# main.net
KiCad netlist of a schematic drawn in Altium Designer
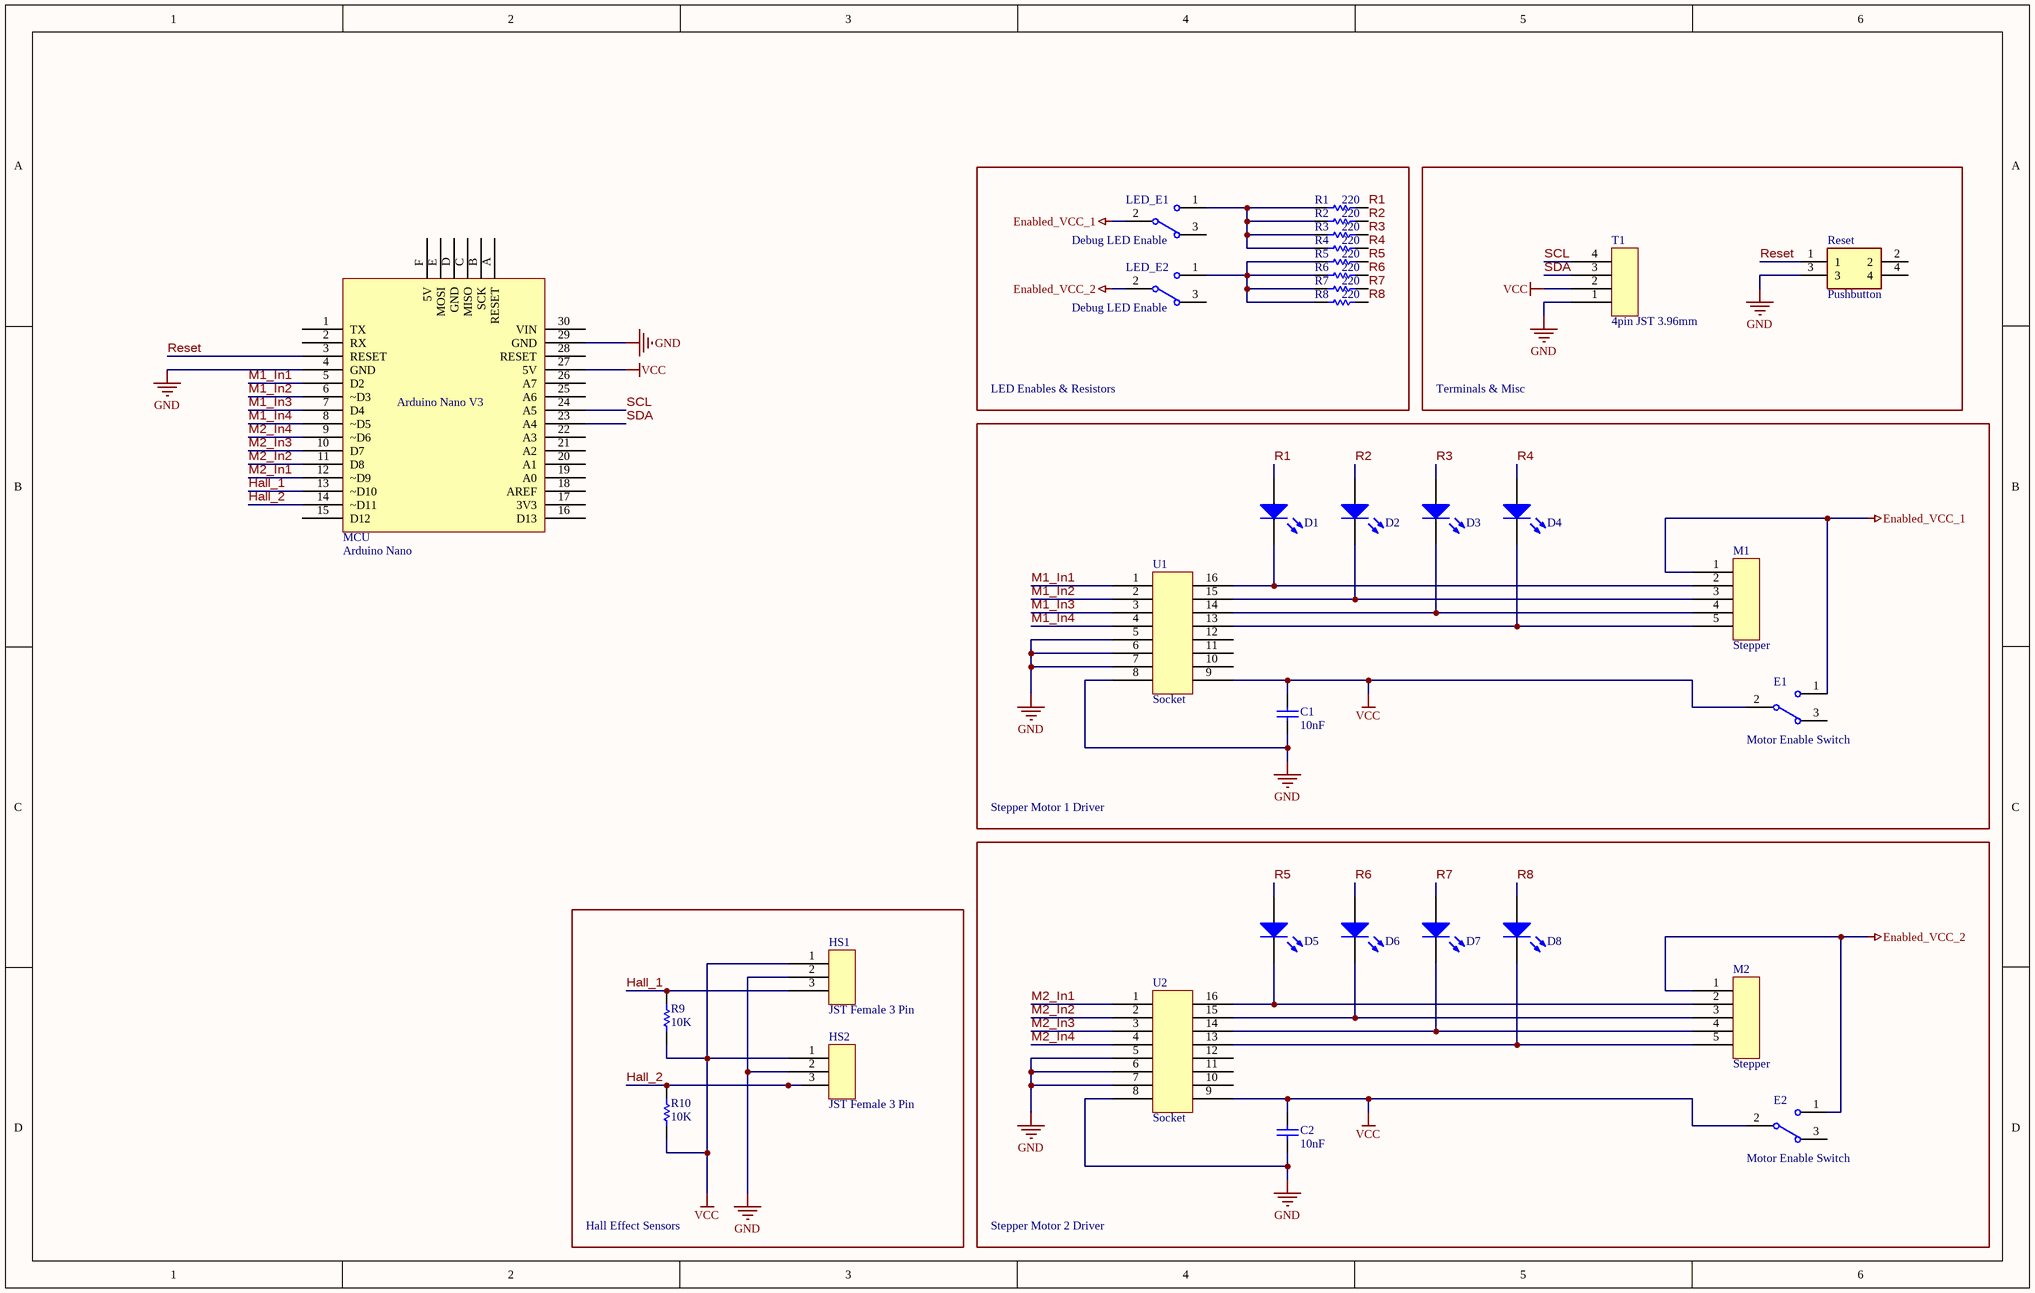
[diagram p0: main.SchDoc]

(export (version "E")
  (design (tool "Eeschema 10.0.6"))
  (components
    (comp (ref "C1")
      (value "Thru-Hole Cap")
      (footprint "Nonpolarized cap")
      (description "Nonpolarized capacitor")
      (fields (field (name "CAPACITANCE") "10nF"))
      (libsource (lib "Misc Components") (part "Thru-Hole Cap"))
    )
    (comp (ref "C2")
      (value "Thru-Hole Cap")
      (footprint "Nonpolarized cap")
      (description "Nonpolarized capacitor")
      (fields (field (name "CAPACITANCE") "10nF"))
      (libsource (lib "Misc Components") (part "Thru-Hole Cap"))
    )
    (comp (ref "D1")
      (value "LED")
      (footprint "Small Blue LED")
      (description "3mm LED")
      (libsource (lib "Misc Components") (part "Small LED"))
    )
    (comp (ref "D2")
      (value "LED")
      (footprint "Small Green LED")
      (description "3mm LED")
      (libsource (lib "Misc Components") (part "Small LED"))
    )
    (comp (ref "D3")
      (value "LED")
      (footprint "Small Orange LED")
      (description "3mm LED")
      (libsource (lib "Misc Components") (part "Small LED"))
    )
    (comp (ref "D4")
      (value "LED")
      (footprint "Small Yellow LED")
      (description "3mm LED")
      (libsource (lib "Misc Components") (part "Small LED"))
    )
    (comp (ref "D5")
      (value "LED")
      (footprint "Small Blue LED")
      (description "3mm LED")
      (libsource (lib "Misc Components") (part "Small LED"))
    )
    (comp (ref "D6")
      (value "LED")
      (footprint "Small Green LED")
      (description "3mm LED")
      (libsource (lib "Misc Components") (part "Small LED"))
    )
    (comp (ref "D7")
      (value "LED")
      (footprint "Small Orange LED")
      (description "3mm LED")
      (libsource (lib "Misc Components") (part "Small LED"))
    )
    (comp (ref "D8")
      (value "LED")
      (footprint "Small Yellow LED")
      (description "3mm LED")
      (libsource (lib "Misc Components") (part "Small LED"))
    )
    (comp (ref "E1")
      (value "Motor Enable Switch")
      (footprint "SPDT Switch")
      (libsource (lib "Misc Components") (part "SPDT Switch"))
    )
    (comp (ref "E2")
      (value "Motor Enable Switch")
      (footprint "SPDT Switch")
      (libsource (lib "Misc Components") (part "SPDT Switch"))
    )
    (comp (ref "HS1")
      (value "JST Female 3 Pin")
      (footprint "Jst Female 3pin")
      (libsource (lib "Misc Components") (part "JST Female 3 Pin"))
    )
    (comp (ref "HS2")
      (value "JST Female 3 Pin")
      (footprint "Jst Female 3pin")
      (libsource (lib "Misc Components") (part "JST Female 3 Pin"))
    )
    (comp (ref "LED_E1")
      (value "Debug LED Enable")
      (footprint "SPDT Switch")
      (libsource (lib "Misc Components") (part "SPDT Switch"))
    )
    (comp (ref "LED_E2")
      (value "Debug LED Enable")
      (footprint "SPDT Switch")
      (libsource (lib "Misc Components") (part "SPDT Switch"))
    )
    (comp (ref "M1")
      (value "Stepper")
      (footprint "JST Female 5pin")
      (libsource (lib "Misc Components") (part "JST Female 5 Pin"))
    )
    (comp (ref "M2")
      (value "Stepper")
      (footprint "JST Female 5pin")
      (libsource (lib "Misc Components") (part "JST Female 5 Pin"))
    )
    (comp (ref "MCU")
      (value "Arduino Nano")
      (footprint "Arduino Nano")
      (libsource (lib "Detailed Arduino") (part "Arduino Nano"))
    )
    (comp (ref "R1")
      (value "220")
      (footprint "AXIAL-0.3")
      (description "Resistor")
      (fields (field (name "Comment") "Res1") (field (name "PUBLISHER") "Altium Limited"))
      (libsource (lib "Miscellaneous Devices") (part "Res1"))
    )
    (comp (ref "R2")
      (value "220")
      (footprint "AXIAL-0.3")
      (description "Resistor")
      (fields (field (name "Comment") "Res1") (field (name "PUBLISHER") "Altium Limited"))
      (libsource (lib "Miscellaneous Devices") (part "Res1"))
    )
    (comp (ref "R3")
      (value "220")
      (footprint "AXIAL-0.3")
      (description "Resistor")
      (fields (field (name "Comment") "Res1") (field (name "PUBLISHER") "Altium Limited"))
      (libsource (lib "Miscellaneous Devices") (part "Res1"))
    )
    (comp (ref "R4")
      (value "220")
      (footprint "AXIAL-0.3")
      (description "Resistor")
      (fields (field (name "Comment") "Res1") (field (name "PUBLISHER") "Altium Limited"))
      (libsource (lib "Miscellaneous Devices") (part "Res1"))
    )
    (comp (ref "R5")
      (value "220")
      (footprint "AXIAL-0.3")
      (description "Resistor")
      (fields (field (name "Comment") "Res1") (field (name "PUBLISHER") "Altium Limited"))
      (libsource (lib "Miscellaneous Devices") (part "Res1"))
    )
    (comp (ref "R6")
      (value "220")
      (footprint "AXIAL-0.3")
      (description "Resistor")
      (fields (field (name "Comment") "Res1") (field (name "PUBLISHER") "Altium Limited"))
      (libsource (lib "Miscellaneous Devices") (part "Res1"))
    )
    (comp (ref "R7")
      (value "220")
      (footprint "AXIAL-0.3")
      (description "Resistor")
      (fields (field (name "Comment") "Res1") (field (name "PUBLISHER") "Altium Limited"))
      (libsource (lib "Miscellaneous Devices") (part "Res1"))
    )
    (comp (ref "R8")
      (value "220")
      (footprint "AXIAL-0.3")
      (description "Resistor")
      (fields (field (name "Comment") "Res1") (field (name "PUBLISHER") "Altium Limited"))
      (libsource (lib "Miscellaneous Devices") (part "Res1"))
    )
    (comp (ref "R9")
      (value "10K")
      (footprint "AXIAL-0.3")
      (description "Resistor")
      (fields (field (name "Comment") "Res1") (field (name "PUBLISHER") "Altium Limited"))
      (libsource (lib "Miscellaneous Devices") (part "Res1"))
    )
    (comp (ref "R10")
      (value "10K")
      (footprint "AXIAL-0.3")
      (description "Resistor")
      (fields (field (name "Comment") "Res1") (field (name "PUBLISHER") "Altium Limited"))
      (libsource (lib "Miscellaneous Devices") (part "Res1"))
    )
    (comp (ref "Reset")
      (value "Pushbutton")
      (footprint "SamacSys:FSM4JH")
      (description "Switch")
      (fields
        (field (name "MANUFACTURER_PART_NUMBER") "FSM2JAH")
        (field (name "MOUSER PART NUMBER") "506-FSM2JAH")
      )
      (libsource (lib "SamacSys") (part "Pushbutton"))
    )
    (comp (ref "T1")
      (value "4pin JST 3.96mm")
      (footprint "JST VH 3.96mm 4pin Female Connector")
      (libsource (lib "Misc Components") (part "JST VH 3.96mm 4pin Female Connector"))
    )
    (comp (ref "U1")
      (value "Socket")
      (footprint "SamacSys:16pin DIP IC Socket")
      (description "Integrated Circuit")
      (fields
        (field (name "MANUFACTURER_PART_NUMBER") "1-2199298-4")
        (field (name "MOUSER PART NUMBER") "571-1-2199298-4")
      )
      (libsource (lib "SamacSys") (part "1-2199298-4"))
    )
    (comp (ref "U2")
      (value "Socket")
      (footprint "SamacSys:16pin DIP IC Socket")
      (description "Integrated Circuit")
      (fields
        (field (name "MANUFACTURER_PART_NUMBER") "1-2199298-4")
        (field (name "MOUSER PART NUMBER") "571-1-2199298-4")
      )
      (libsource (lib "SamacSys") (part "1-2199298-4"))
    )
  )
  (nets
    (net (code "1") (name "/Hall_1") (class "Default")
      (node (ref "HS1") (pin "3") (pintype "power_in"))
      (node (ref "MCU") (pin "13") (pinfunction "~D10_13") (pintype "power_in"))
      (node (ref "R9") (pin "1") (pinfunction "1_1") (pintype "passive"))
    )
    (net (code "2") (name "/Hall_2") (class "Default")
      (node (ref "HS2") (pin "3") (pintype "power_in"))
      (node (ref "MCU") (pin "14") (pinfunction "~D11_14") (pintype "power_in"))
      (node (ref "R10") (pin "1") (pinfunction "1_1") (pintype "passive"))
    )
    (net (code "3") (name "/M1_In1") (class "Default")
      (node (ref "MCU") (pin "5") (pinfunction "D2_5") (pintype "power_in"))
      (node (ref "U1") (pin "1") (pintype "power_in"))
    )
    (net (code "4") (name "/M1_In2") (class "Default")
      (node (ref "MCU") (pin "6") (pinfunction "~D3_6") (pintype "power_in"))
      (node (ref "U1") (pin "2") (pintype "power_in"))
    )
    (net (code "5") (name "/M1_In3") (class "Default")
      (node (ref "MCU") (pin "7") (pinfunction "D4_7") (pintype "power_in"))
      (node (ref "U1") (pin "3") (pintype "power_in"))
    )
    (net (code "6") (name "/M1_In4") (class "Default")
      (node (ref "MCU") (pin "8") (pinfunction "~D5_8") (pintype "power_in"))
      (node (ref "U1") (pin "4") (pintype "power_in"))
    )
    (net (code "7") (name "/M2_In1") (class "Default")
      (node (ref "MCU") (pin "12") (pinfunction "~D9_12") (pintype "power_in"))
      (node (ref "U2") (pin "1") (pintype "power_in"))
    )
    (net (code "8") (name "/M2_In2") (class "Default")
      (node (ref "MCU") (pin "11") (pinfunction "D8_11") (pintype "power_in"))
      (node (ref "U2") (pin "2") (pintype "power_in"))
    )
    (net (code "9") (name "/M2_In3") (class "Default")
      (node (ref "MCU") (pin "10") (pinfunction "D7_10") (pintype "power_in"))
      (node (ref "U2") (pin "3") (pintype "power_in"))
    )
    (net (code "10") (name "/M2_In4") (class "Default")
      (node (ref "MCU") (pin "9") (pinfunction "~D6_9") (pintype "power_in"))
      (node (ref "U2") (pin "4") (pintype "power_in"))
    )
    (net (code "11") (name "/R1") (class "Default")
      (node (ref "D1") (pin "1") (pinfunction "A_1") (pintype "passive"))
      (node (ref "R1") (pin "2") (pinfunction "2_2") (pintype "passive"))
    )
    (net (code "12") (name "/R2") (class "Default")
      (node (ref "D2") (pin "1") (pinfunction "A_1") (pintype "passive"))
      (node (ref "R2") (pin "2") (pinfunction "2_2") (pintype "passive"))
    )
    (net (code "13") (name "/R3") (class "Default")
      (node (ref "D3") (pin "1") (pinfunction "A_1") (pintype "passive"))
      (node (ref "R3") (pin "2") (pinfunction "2_2") (pintype "passive"))
    )
    (net (code "14") (name "/R4") (class "Default")
      (node (ref "D4") (pin "1") (pinfunction "A_1") (pintype "passive"))
      (node (ref "R4") (pin "2") (pinfunction "2_2") (pintype "passive"))
    )
    (net (code "15") (name "/R5") (class "Default")
      (node (ref "D5") (pin "1") (pinfunction "A_1") (pintype "passive"))
      (node (ref "R5") (pin "2") (pinfunction "2_2") (pintype "passive"))
    )
    (net (code "16") (name "/R6") (class "Default")
      (node (ref "D6") (pin "1") (pinfunction "A_1") (pintype "passive"))
      (node (ref "R6") (pin "2") (pinfunction "2_2") (pintype "passive"))
    )
    (net (code "17") (name "/R7") (class "Default")
      (node (ref "D7") (pin "1") (pinfunction "A_1") (pintype "passive"))
      (node (ref "R7") (pin "2") (pinfunction "2_2") (pintype "passive"))
    )
    (net (code "18") (name "/R8") (class "Default")
      (node (ref "D8") (pin "1") (pinfunction "A_1") (pintype "passive"))
      (node (ref "R8") (pin "2") (pinfunction "2_2") (pintype "passive"))
    )
    (net (code "19") (name "/Reset") (class "Default")
      (node (ref "MCU") (pin "3") (pinfunction "RESET_3") (pintype "power_in"))
      (node (ref "Reset") (pin "1") (pinfunction "1_1") (pintype "passive"))
    )
    (net (code "20") (name "/SCL") (class "Default")
      (node (ref "MCU") (pin "24") (pinfunction "A5_24") (pintype "power_in"))
      (node (ref "T1") (pin "4") (pintype "power_in"))
    )
    (net (code "21") (name "/SDA") (class "Default")
      (node (ref "MCU") (pin "23") (pinfunction "A4_23") (pintype "power_in"))
      (node (ref "T1") (pin "3") (pintype "power_in"))
    )
    (net (code "22") (name "Enabled_VCC_1") (class "Default")
      (node (ref "E1") (pin "1") (pinfunction "1_1") (pintype "passive"))
      (node (ref "LED_E1") (pin "2") (pinfunction "2_2") (pintype "passive"))
      (node (ref "M1") (pin "1") (pintype "power_in"))
    )
    (net (code "23") (name "Enabled_VCC_2") (class "Default")
      (node (ref "E2") (pin "1") (pinfunction "1_1") (pintype "passive"))
      (node (ref "LED_E2") (pin "2") (pinfunction "2_2") (pintype "passive"))
      (node (ref "M2") (pin "1") (pintype "power_in"))
    )
    (net (code "24") (name "GND") (class "Default")
      (node (ref "C1") (pin "1") (pinfunction "1_1") (pintype "passive"))
      (node (ref "C2") (pin "1") (pinfunction "1_1") (pintype "passive"))
      (node (ref "HS1") (pin "2") (pintype "power_in"))
      (node (ref "HS2") (pin "2") (pintype "power_in"))
      (node (ref "MCU") (pin "29") (pinfunction "GND_29") (pintype "power_in"))
      (node (ref "MCU") (pin "4") (pinfunction "GND_4") (pintype "power_in"))
      (node (ref "Reset") (pin "3") (pinfunction "3_3") (pintype "passive"))
      (node (ref "T1") (pin "1") (pintype "power_in"))
      (node (ref "U1") (pin "5") (pintype "power_in"))
      (node (ref "U1") (pin "6") (pintype "power_in"))
      (node (ref "U1") (pin "7") (pintype "power_in"))
      (node (ref "U1") (pin "8") (pintype "power_in"))
      (node (ref "U2") (pin "5") (pintype "power_in"))
      (node (ref "U2") (pin "6") (pintype "power_in"))
      (node (ref "U2") (pin "7") (pintype "power_in"))
      (node (ref "U2") (pin "8") (pintype "power_in"))
    )
    (net (code "25") (name "Net-(D1-K)") (class "Default")
      (node (ref "D1") (pin "2") (pinfunction "K_2") (pintype "passive"))
      (node (ref "M1") (pin "2") (pintype "power_in"))
      (node (ref "U1") (pin "16") (pintype "power_in"))
    )
    (net (code "26") (name "Net-(D2-K)") (class "Default")
      (node (ref "D2") (pin "2") (pinfunction "K_2") (pintype "passive"))
      (node (ref "M1") (pin "3") (pintype "power_in"))
      (node (ref "U1") (pin "15") (pintype "power_in"))
    )
    (net (code "27") (name "Net-(D3-K)") (class "Default")
      (node (ref "D3") (pin "2") (pinfunction "K_2") (pintype "passive"))
      (node (ref "M1") (pin "4") (pintype "power_in"))
      (node (ref "U1") (pin "14") (pintype "power_in"))
    )
    (net (code "28") (name "Net-(D4-K)") (class "Default")
      (node (ref "D4") (pin "2") (pinfunction "K_2") (pintype "passive"))
      (node (ref "M1") (pin "5") (pintype "power_in"))
      (node (ref "U1") (pin "13") (pintype "power_in"))
    )
    (net (code "29") (name "Net-(D5-K)") (class "Default")
      (node (ref "D5") (pin "2") (pinfunction "K_2") (pintype "passive"))
      (node (ref "M2") (pin "2") (pintype "power_in"))
      (node (ref "U2") (pin "16") (pintype "power_in"))
    )
    (net (code "30") (name "Net-(D6-K)") (class "Default")
      (node (ref "D6") (pin "2") (pinfunction "K_2") (pintype "passive"))
      (node (ref "M2") (pin "3") (pintype "power_in"))
      (node (ref "U2") (pin "15") (pintype "power_in"))
    )
    (net (code "31") (name "Net-(D7-K)") (class "Default")
      (node (ref "D7") (pin "2") (pinfunction "K_2") (pintype "passive"))
      (node (ref "M2") (pin "4") (pintype "power_in"))
      (node (ref "U2") (pin "14") (pintype "power_in"))
    )
    (net (code "32") (name "Net-(D8-K)") (class "Default")
      (node (ref "D8") (pin "2") (pinfunction "K_2") (pintype "passive"))
      (node (ref "M2") (pin "5") (pintype "power_in"))
      (node (ref "U2") (pin "13") (pintype "power_in"))
    )
    (net (code "33") (name "Net-(LED_E1-Pad1)") (class "Default")
      (node (ref "LED_E1") (pin "1") (pinfunction "1_1") (pintype "passive"))
      (node (ref "R1") (pin "1") (pinfunction "1_1") (pintype "passive"))
      (node (ref "R2") (pin "1") (pinfunction "1_1") (pintype "passive"))
      (node (ref "R3") (pin "1") (pinfunction "1_1") (pintype "passive"))
      (node (ref "R4") (pin "1") (pinfunction "1_1") (pintype "passive"))
    )
    (net (code "34") (name "Net-(LED_E2-Pad1)") (class "Default")
      (node (ref "LED_E2") (pin "1") (pinfunction "1_1") (pintype "passive"))
      (node (ref "R5") (pin "1") (pinfunction "1_1") (pintype "passive"))
      (node (ref "R6") (pin "1") (pinfunction "1_1") (pintype "passive"))
      (node (ref "R7") (pin "1") (pinfunction "1_1") (pintype "passive"))
      (node (ref "R8") (pin "1") (pinfunction "1_1") (pintype "passive"))
    )
    (net (code "35") (name "VCC") (class "Default")
      (node (ref "C1") (pin "2") (pinfunction "2_2") (pintype "passive"))
      (node (ref "C2") (pin "2") (pinfunction "2_2") (pintype "passive"))
      (node (ref "E1") (pin "2") (pinfunction "2_2") (pintype "passive"))
      (node (ref "E2") (pin "2") (pinfunction "2_2") (pintype "passive"))
      (node (ref "HS1") (pin "1") (pintype "power_in"))
      (node (ref "HS2") (pin "1") (pintype "power_in"))
      (node (ref "MCU") (pin "27") (pinfunction "5V_27") (pintype "power_in"))
      (node (ref "R10") (pin "2") (pinfunction "2_2") (pintype "passive"))
      (node (ref "R9") (pin "2") (pinfunction "2_2") (pintype "passive"))
      (node (ref "T1") (pin "2") (pintype "power_in"))
      (node (ref "U1") (pin "9") (pintype "power_in"))
      (node (ref "U2") (pin "9") (pintype "power_in"))
    )
    (net (code "36") (name "unconnected-(E1-Pad3)") (class "Default")
      (node (ref "E1") (pin "3") (pinfunction "3_3") (pintype "passive"))
    )
    (net (code "37") (name "unconnected-(E2-Pad3)") (class "Default")
      (node (ref "E2") (pin "3") (pinfunction "3_3") (pintype "passive"))
    )
    (net (code "38") (name "unconnected-(LED_E1-Pad3)") (class "Default")
      (node (ref "LED_E1") (pin "3") (pinfunction "3_3") (pintype "passive"))
    )
    (net (code "39") (name "unconnected-(LED_E2-Pad3)") (class "Default")
      (node (ref "LED_E2") (pin "3") (pinfunction "3_3") (pintype "passive"))
    )
    (net (code "40") (name "unconnected-(MCU-3V3-Pad17)") (class "Default")
      (node (ref "MCU") (pin "17") (pinfunction "3V3_17") (pintype "power_in"))
    )
    (net (code "41") (name "unconnected-(MCU-5V-PadF)") (class "Default")
      (node (ref "MCU") (pin "F") (pinfunction "5V_F") (pintype "power_in"))
    )
    (net (code "42") (name "unconnected-(MCU-A0-Pad19)") (class "Default")
      (node (ref "MCU") (pin "19") (pinfunction "A0_19") (pintype "power_in"))
    )
    (net (code "43") (name "unconnected-(MCU-A1-Pad20)") (class "Default")
      (node (ref "MCU") (pin "20") (pinfunction "A1_20") (pintype "power_in"))
    )
    (net (code "44") (name "unconnected-(MCU-A2-Pad21)") (class "Default")
      (node (ref "MCU") (pin "21") (pinfunction "A2_21") (pintype "power_in"))
    )
    (net (code "45") (name "unconnected-(MCU-A3-Pad22)") (class "Default")
      (node (ref "MCU") (pin "22") (pinfunction "A3_22") (pintype "power_in"))
    )
    (net (code "46") (name "unconnected-(MCU-A6-Pad25)") (class "Default")
      (node (ref "MCU") (pin "25") (pinfunction "A6_25") (pintype "power_in"))
    )
    (net (code "47") (name "unconnected-(MCU-A7-Pad26)") (class "Default")
      (node (ref "MCU") (pin "26") (pinfunction "A7_26") (pintype "power_in"))
    )
    (net (code "48") (name "unconnected-(MCU-AREF-Pad18)") (class "Default")
      (node (ref "MCU") (pin "18") (pinfunction "AREF_18") (pintype "power_in"))
    )
    (net (code "49") (name "unconnected-(MCU-D12-Pad15)") (class "Default")
      (node (ref "MCU") (pin "15") (pinfunction "D12_15") (pintype "power_in"))
    )
    (net (code "50") (name "unconnected-(MCU-D13-Pad16)") (class "Default")
      (node (ref "MCU") (pin "16") (pinfunction "D13_16") (pintype "power_in"))
    )
    (net (code "51") (name "unconnected-(MCU-GND-PadD)") (class "Default")
      (node (ref "MCU") (pin "D") (pinfunction "GND_D") (pintype "power_in"))
    )
    (net (code "52") (name "unconnected-(MCU-MISO-PadC)") (class "Default")
      (node (ref "MCU") (pin "C") (pinfunction "MISO_C") (pintype "power_in"))
    )
    (net (code "53") (name "unconnected-(MCU-MOSI-PadE)") (class "Default")
      (node (ref "MCU") (pin "E") (pinfunction "MOSI_E") (pintype "power_in"))
    )
    (net (code "54") (name "unconnected-(MCU-RESET-Pad28)") (class "Default")
      (node (ref "MCU") (pin "28") (pinfunction "RESET_28") (pintype "power_in"))
    )
    (net (code "55") (name "unconnected-(MCU-RESET-PadA)") (class "Default")
      (node (ref "MCU") (pin "A") (pinfunction "RESET_A") (pintype "power_in"))
    )
    (net (code "56") (name "unconnected-(MCU-RX-Pad2)") (class "Default")
      (node (ref "MCU") (pin "2") (pinfunction "RX_2") (pintype "power_in"))
    )
    (net (code "57") (name "unconnected-(MCU-SCK-PadB)") (class "Default")
      (node (ref "MCU") (pin "B") (pinfunction "SCK_B") (pintype "power_in"))
    )
    (net (code "58") (name "unconnected-(MCU-TX-Pad1)") (class "Default")
      (node (ref "MCU") (pin "1") (pinfunction "TX_1") (pintype "power_in"))
    )
    (net (code "59") (name "unconnected-(MCU-VIN-Pad30)") (class "Default")
      (node (ref "MCU") (pin "30") (pinfunction "VIN_30") (pintype "power_in"))
    )
    (net (code "60") (name "unconnected-(Reset-Pad2)") (class "Default")
      (node (ref "Reset") (pin "2") (pinfunction "2_2") (pintype "passive"))
    )
    (net (code "61") (name "unconnected-(Reset-Pad4)") (class "Default")
      (node (ref "Reset") (pin "4") (pinfunction "4_4") (pintype "passive"))
    )
    (net (code "62") (name "unconnected-(U1-Pad10)") (class "Default")
      (node (ref "U1") (pin "10") (pintype "power_in"))
    )
    (net (code "63") (name "unconnected-(U1-Pad11)") (class "Default")
      (node (ref "U1") (pin "11") (pintype "power_in"))
    )
    (net (code "64") (name "unconnected-(U1-Pad12)") (class "Default")
      (node (ref "U1") (pin "12") (pintype "power_in"))
    )
    (net (code "65") (name "unconnected-(U2-Pad10)") (class "Default")
      (node (ref "U2") (pin "10") (pintype "power_in"))
    )
    (net (code "66") (name "unconnected-(U2-Pad11)") (class "Default")
      (node (ref "U2") (pin "11") (pintype "power_in"))
    )
    (net (code "67") (name "unconnected-(U2-Pad12)") (class "Default")
      (node (ref "U2") (pin "12") (pintype "power_in"))
    )
  )
)
